# BLE.net
KiCad netlist of a schematic drawn in Altium Designer
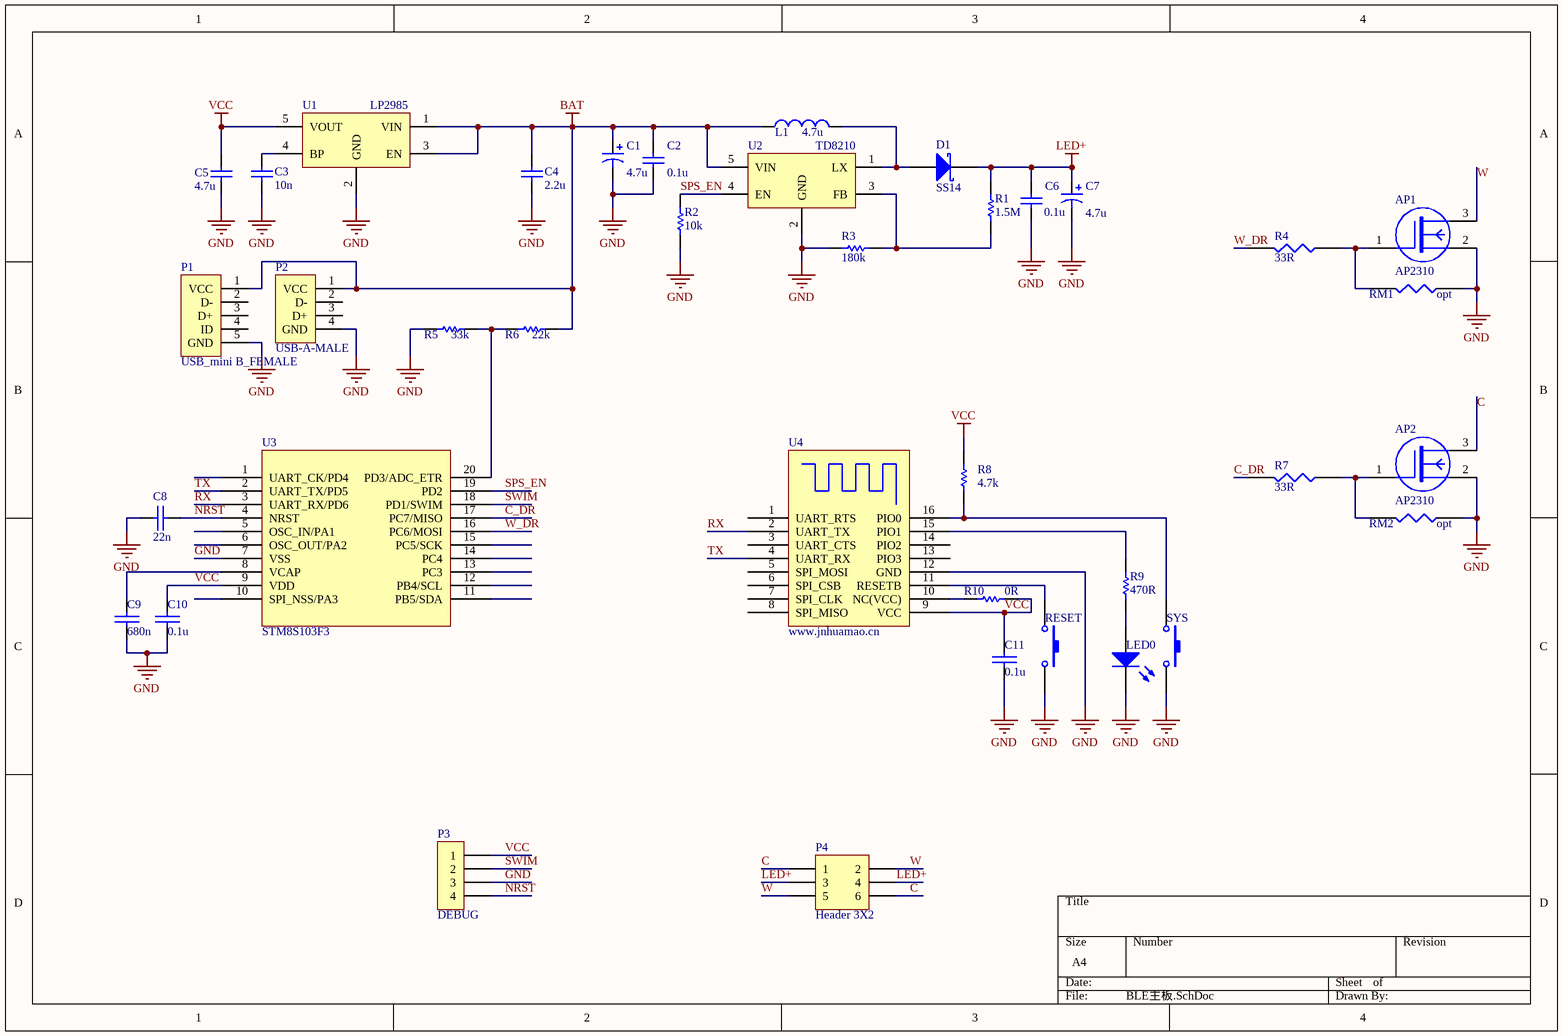
[diagram p0: BLE主板.SchDoc]

(export (version "E")
  (design (tool "Eeschema 10.0.6"))
  (components
    (comp (ref "AP1") (value "AP2310") (footprint "SOT23-3N") (libsource (lib "*") (part "MOSFET-N1")))
    (comp (ref "AP2") (value "AP2310") (footprint "SOT23-3N") (libsource (lib "*") (part "MOSFET-N1")))
    (comp (ref "C1")
      (value "4.7u")
      (footprint "2012[0805]")
      (description "Polarized Capacitor (Radial)")
      (fields (field (name "PUBLISHER") "Altium Limited"))
      (libsource (lib "Miscellaneous Devices") (part "Cap Pol1"))
    )
    (comp (ref "C2")
      (value "0.1u")
      (footprint "2012[0805]")
      (description "Capacitor")
      (fields (field (name "PUBLISHER") "Altium Limited"))
      (libsource (lib "Miscellaneous Devices") (part "Cap"))
    )
    (comp (ref "C3")
      (value "10n")
      (footprint "2012[0805]")
      (description "Capacitor")
      (fields (field (name "PUBLISHER") "Altium Limited"))
      (libsource (lib "Miscellaneous Devices") (part "Cap"))
    )
    (comp (ref "C4")
      (value "2.2u")
      (footprint "2012[0805]")
      (description "Capacitor")
      (fields (field (name "PUBLISHER") "Altium Limited"))
      (libsource (lib "Miscellaneous Devices") (part "Cap"))
    )
    (comp (ref "C5")
      (value "4.7u")
      (footprint "2012[0805]")
      (description "Capacitor")
      (fields (field (name "PUBLISHER") "Altium Limited"))
      (libsource (lib "Miscellaneous Devices") (part "Cap"))
    )
    (comp (ref "C6")
      (value "0.1u")
      (footprint "2012[0805]")
      (description "Capacitor")
      (fields (field (name "PUBLISHER") "Altium Limited"))
      (libsource (lib "Miscellaneous Devices") (part "Cap"))
    )
    (comp (ref "C7")
      (value "4.7u")
      (footprint "2012[0805]")
      (description "Polarized Capacitor (Radial)")
      (fields (field (name "PUBLISHER") "Altium Limited"))
      (libsource (lib "Miscellaneous Devices") (part "Cap Pol1"))
    )
    (comp (ref "C8")
      (value "22n")
      (footprint "2012[0805]")
      (description "Capacitor")
      (libsource (lib "*") (part "CAP"))
    )
    (comp (ref "C9")
      (value "680n")
      (footprint "2012[0805]")
      (description "Capacitor")
      (libsource (lib "*") (part "CAP"))
    )
    (comp (ref "C10")
      (value "0.1u")
      (footprint "2012[0805]")
      (description "Capacitor")
      (libsource (lib "*") (part "CAP"))
    )
    (comp (ref "C11")
      (value "0.1u")
      (footprint "2012[0805]")
      (description "Capacitor")
      (libsource (lib "*") (part "CAP"))
    )
    (comp (ref "D1")
      (value "SS14")
      (footprint "DIOM4227X23N[DO-214AC(SMA)]")
      (description "Schottky Diode")
      (fields (field (name "PUBLISHER") "Altium Limited"))
      (libsource (lib "Miscellaneous Devices") (part "D Schottky"))
    )
    (comp (ref "DS1")
      (value "LED0")
      (footprint "RESC2012N")
      (description "Typical INFRARED GaAs LED")
      (fields (field (name "PUBLISHER") "Altium Limited"))
      (libsource (lib "Miscellaneous Devices") (part "LED0"))
    )
    (comp (ref "L1")
      (value "4.7u")
      (footprint "INDP7070X40N")
      (description "Inductor")
      (fields (field (name "PUBLISHER") "Altium Limited"))
      (libsource (lib "Miscellaneous Devices") (part "Inductor"))
    )
    (comp (ref "P1")
      (value "USB_mini B_FEMALE")
      (footprint "USB/SM0.8-6H5")
      (description "Header, 5-Pin")
      (fields (field (name "PUBLISHER") "Altium Limited"))
      (libsource (lib "Miscellaneous Connectors") (part "Header 5"))
    )
    (comp (ref "P2")
      (value "USB-A-MALE")
      (footprint "USB/SM2.5-4H4")
      (description "Header, 4-Pin")
      (fields (field (name "PUBLISHER") "Altium Limited"))
      (libsource (lib "Miscellaneous Connectors") (part "Header 4"))
    )
    (comp (ref "P3")
      (value "DEBUG")
      (footprint "HDR1X4")
      (description "Connector")
      (libsource (lib "*") (part "CON4"))
    )
    (comp (ref "P4")
      (value "Header 3X2")
      (footprint "HDR2X3")
      (description "Header, 3-Pin, Dual row")
      (fields (field (name "PUBLISHER") "Altium Limited"))
      (libsource (lib "Miscellaneous Connectors") (part "Header 3X2"))
    )
    (comp (ref "R1")
      (value "1.5M")
      (footprint "2012[0805]")
      (description "Resistor")
      (fields (field (name "PUBLISHER") "Altium Limited"))
      (libsource (lib "") (part "Res1_1"))
    )
    (comp (ref "R2")
      (value "10k")
      (footprint "2012[0805]")
      (description "Resistor")
      (fields (field (name "PUBLISHER") "Altium Limited"))
      (libsource (lib "") (part "Res1_1"))
    )
    (comp (ref "R3")
      (value "180k")
      (footprint "2012[0805]")
      (description "Resistor")
      (fields (field (name "PUBLISHER") "Altium Limited"))
      (libsource (lib "") (part "Res1_1"))
    )
    (comp (ref "R4") (value "33R") (footprint "2012[0805]") (libsource (lib "*") (part "RES1")))
    (comp (ref "R5")
      (value "33k")
      (footprint "2012[0805]")
      (description "Resistor")
      (fields (field (name "PUBLISHER") "Altium Limited"))
      (libsource (lib "") (part "Res1_1"))
    )
    (comp (ref "R6")
      (value "22k")
      (footprint "2012[0805]")
      (description "Resistor")
      (fields (field (name "PUBLISHER") "Altium Limited"))
      (libsource (lib "") (part "Res1_1"))
    )
    (comp (ref "R7") (value "33R") (footprint "2012[0805]") (libsource (lib "*") (part "RES1")))
    (comp (ref "R8")
      (value "4.7k")
      (footprint "2012[0805]")
      (description "Resistor")
      (fields (field (name "PUBLISHER") "Altium Limited"))
      (libsource (lib "Miscellaneous Devices") (part "Res1"))
    )
    (comp (ref "R9")
      (value "470R")
      (footprint "2012[0805]")
      (description "Resistor")
      (fields (field (name "Comment") "Res1") (field (name "PUBLISHER") "Altium Limited"))
      (libsource (lib "Miscellaneous Devices") (part "Res1"))
    )
    (comp (ref "R10")
      (value "0R")
      (footprint "2012[0805]")
      (description "Resistor")
      (fields (field (name "PUBLISHER") "Altium Limited"))
      (libsource (lib "") (part "Res1_1"))
    )
    (comp (ref "RM1") (value "opt") (footprint "2012[0805]") (libsource (lib "*") (part "RES1")))
    (comp (ref "RM2") (value "opt") (footprint "2012[0805]") (libsource (lib "*") (part "RES1")))
    (comp (ref "S1")
      (value "RESET")
      (footprint "微动开关")
      (description "Switch")
      (fields (field (name "PUBLISHER") "Altium Limited"))
      (libsource (lib "Miscellaneous Devices") (part "SW-PB"))
    )
    (comp (ref "S2")
      (value "SYS")
      (footprint "微动开关")
      (description "Switch")
      (fields (field (name "PUBLISHER") "Altium Limited"))
      (libsource (lib "Miscellaneous Devices") (part "SW-PB"))
    )
    (comp (ref "U1") (value "LP2985") (footprint "SOT23-5AN") (libsource (lib "My Library") (part "LP2985")))
    (comp (ref "U2") (value "TD8210") (footprint "SOT23-5AN") (libsource (lib "My Library") (part "TD8210")))
    (comp (ref "U3")
      (value "STM8S103F3")
      (footprint "TSOP65P640-20BN")
      (libsource (lib "*") (part "Component_1"))
    )
    (comp (ref "U4")
      (value "www.jnhuamao.cn")
      (footprint "HM_05_06_07_11")
      (description "HM bluetooth module HM-05,HM-06,HM-07, HM-11")
      (libsource (lib "My Library") (part "HM_05_06_07_11"))
    )
  )
  (nets
    (net (code "1") (name "/C") (class "Default")
      (node (ref "AP2") (pin "3") (pinfunction "D_3") (pintype "passive"))
      (node (ref "P4") (pin "1") (pinfunction "1_1") (pintype "passive"))
      (node (ref "P4") (pin "6") (pinfunction "6_6") (pintype "passive"))
    )
    (net (code "2") (name "/C_DR") (class "Default")
      (node (ref "R7") (pin "2") (pinfunction "2_2") (pintype "passive"))
      (node (ref "U3") (pin "17") (pinfunction "PC7/MISO_17") (pintype "passive"))
    )
    (net (code "3") (name "/NRST") (class "Default")
      (node (ref "C8") (pin "2") (pinfunction "2_2") (pintype "passive"))
      (node (ref "P3") (pin "4") (pinfunction "4_4") (pintype "passive"))
      (node (ref "U3") (pin "4") (pinfunction "NRST_4") (pintype "passive"))
    )
    (net (code "4") (name "/RX") (class "Default")
      (node (ref "U3") (pin "3") (pinfunction "UART_RX/PD6_3") (pintype "passive"))
      (node (ref "U4") (pin "2") (pinfunction "UART_TX_2") (pintype "passive"))
    )
    (net (code "5") (name "/SPS_EN") (class "Default")
      (node (ref "R2") (pin "2") (pinfunction "2_2") (pintype "passive"))
      (node (ref "U2") (pin "4") (pinfunction "EN_4") (pintype "passive"))
      (node (ref "U3") (pin "19") (pinfunction "PD2_19") (pintype "passive"))
    )
    (net (code "6") (name "/SWIM") (class "Default")
      (node (ref "P3") (pin "2") (pinfunction "2_2") (pintype "passive"))
      (node (ref "U3") (pin "18") (pinfunction "PD1/SWIM_18") (pintype "passive"))
    )
    (net (code "7") (name "/TX") (class "Default")
      (node (ref "U3") (pin "2") (pinfunction "UART_TX/PD5_2") (pintype "passive"))
      (node (ref "U4") (pin "4") (pinfunction "UART_RX_4") (pintype "passive"))
    )
    (net (code "8") (name "/W") (class "Default")
      (node (ref "AP1") (pin "3") (pinfunction "D_3") (pintype "passive"))
      (node (ref "P4") (pin "2") (pinfunction "2_2") (pintype "passive"))
      (node (ref "P4") (pin "5") (pinfunction "5_5") (pintype "passive"))
    )
    (net (code "9") (name "/W_DR") (class "Default")
      (node (ref "R4") (pin "2") (pinfunction "2_2") (pintype "passive"))
      (node (ref "U3") (pin "16") (pinfunction "PC6/MOSI_16") (pintype "passive"))
    )
    (net (code "10") (name "BAT") (class "Default")
      (node (ref "C1") (pin "1") (pinfunction "1_1") (pintype "passive"))
      (node (ref "C2") (pin "1") (pinfunction "1_1") (pintype "passive"))
      (node (ref "C4") (pin "2") (pinfunction "2_2") (pintype "passive"))
      (node (ref "L1") (pin "1") (pinfunction "1_1") (pintype "passive"))
      (node (ref "P1") (pin "1") (pinfunction "VCC_1") (pintype "passive"))
      (node (ref "P2") (pin "1") (pinfunction "VCC_1") (pintype "passive"))
      (node (ref "R6") (pin "2") (pinfunction "2_2") (pintype "passive"))
      (node (ref "U1") (pin "1") (pinfunction "VIN_1") (pintype "passive"))
      (node (ref "U1") (pin "3") (pinfunction "EN_3") (pintype "passive"))
      (node (ref "U2") (pin "5") (pinfunction "VIN_5") (pintype "passive"))
    )
    (net (code "11") (name "GND") (class "Default")
      (node (ref "AP1") (pin "2") (pinfunction "S_2") (pintype "passive"))
      (node (ref "AP2") (pin "2") (pinfunction "S_2") (pintype "passive"))
      (node (ref "C1") (pin "2") (pinfunction "2_2") (pintype "passive"))
      (node (ref "C10") (pin "1") (pinfunction "1_1") (pintype "passive"))
      (node (ref "C11") (pin "1") (pinfunction "1_1") (pintype "passive"))
      (node (ref "C2") (pin "2") (pinfunction "2_2") (pintype "passive"))
      (node (ref "C3") (pin "1") (pinfunction "1_1") (pintype "passive"))
      (node (ref "C4") (pin "1") (pinfunction "1_1") (pintype "passive"))
      (node (ref "C5") (pin "1") (pinfunction "1_1") (pintype "passive"))
      (node (ref "C6") (pin "1") (pinfunction "1_1") (pintype "passive"))
      (node (ref "C7") (pin "2") (pinfunction "2_2") (pintype "passive"))
      (node (ref "C8") (pin "1") (pinfunction "1_1") (pintype "passive"))
      (node (ref "C9") (pin "1") (pinfunction "1_1") (pintype "passive"))
      (node (ref "DS1") (pin "2") (pinfunction "K_2") (pintype "passive"))
      (node (ref "P1") (pin "5") (pinfunction "GND_5") (pintype "passive"))
      (node (ref "P2") (pin "4") (pinfunction "GND_4") (pintype "passive"))
      (node (ref "P3") (pin "3") (pinfunction "3_3") (pintype "passive"))
      (node (ref "R2") (pin "1") (pinfunction "1_1") (pintype "passive"))
      (node (ref "R3") (pin "1") (pinfunction "1_1") (pintype "passive"))
      (node (ref "R5") (pin "1") (pinfunction "1_1") (pintype "passive"))
      (node (ref "RM1") (pin "1") (pinfunction "1_1") (pintype "passive"))
      (node (ref "RM2") (pin "1") (pinfunction "1_1") (pintype "passive"))
      (node (ref "S1") (pin "2") (pinfunction "2_2") (pintype "passive"))
      (node (ref "S2") (pin "2") (pinfunction "2_2") (pintype "passive"))
      (node (ref "U1") (pin "2") (pinfunction "GND_2") (pintype "passive"))
      (node (ref "U2") (pin "2") (pinfunction "GND_2") (pintype "passive"))
      (node (ref "U3") (pin "7") (pinfunction "VSS_7") (pintype "passive"))
      (node (ref "U4") (pin "12") (pinfunction "GND_12") (pintype "passive"))
    )
    (net (code "12") (name "LED+") (class "Default")
      (node (ref "C6") (pin "2") (pinfunction "2_2") (pintype "passive"))
      (node (ref "C7") (pin "1") (pinfunction "1_1") (pintype "passive"))
      (node (ref "D1") (pin "2") (pinfunction "K_2") (pintype "passive"))
      (node (ref "P4") (pin "3") (pinfunction "3_3") (pintype "passive"))
      (node (ref "P4") (pin "4") (pinfunction "4_4") (pintype "passive"))
      (node (ref "R1") (pin "2") (pinfunction "2_2") (pintype "passive"))
    )
    (net (code "13") (name "Net-(AP1-G)") (class "Default")
      (node (ref "AP1") (pin "1") (pinfunction "G_1") (pintype "passive"))
      (node (ref "R4") (pin "1") (pinfunction "1_1") (pintype "passive"))
      (node (ref "RM1") (pin "2") (pinfunction "2_2") (pintype "passive"))
    )
    (net (code "14") (name "Net-(AP2-G)") (class "Default")
      (node (ref "AP2") (pin "1") (pinfunction "G_1") (pintype "passive"))
      (node (ref "R7") (pin "1") (pinfunction "1_1") (pintype "passive"))
      (node (ref "RM2") (pin "2") (pinfunction "2_2") (pintype "passive"))
    )
    (net (code "15") (name "Net-(D1-A)") (class "Default")
      (node (ref "D1") (pin "1") (pinfunction "A_1") (pintype "passive"))
      (node (ref "L1") (pin "2") (pinfunction "2_2") (pintype "passive"))
      (node (ref "U2") (pin "1") (pinfunction "LX_1") (pintype "passive"))
    )
    (net (code "16") (name "Net-(DS1-A)") (class "Default")
      (node (ref "DS1") (pin "1") (pinfunction "A_1") (pintype "passive"))
      (node (ref "R9") (pin "2") (pinfunction "2_2") (pintype "passive"))
    )
    (net (code "17") (name "Net-(U1-BP)") (class "Default")
      (node (ref "C3") (pin "2") (pinfunction "2_2") (pintype "passive"))
      (node (ref "U1") (pin "4") (pinfunction "BP_4") (pintype "passive"))
    )
    (net (code "18") (name "Net-(U2-FB)") (class "Default")
      (node (ref "R1") (pin "1") (pinfunction "1_1") (pintype "passive"))
      (node (ref "R3") (pin "2") (pinfunction "2_2") (pintype "passive"))
      (node (ref "U2") (pin "3") (pinfunction "FB_3") (pintype "passive"))
    )
    (net (code "19") (name "Net-(U3-PD3{slash}ADC_ETR)") (class "Default")
      (node (ref "R5") (pin "2") (pinfunction "2_2") (pintype "passive"))
      (node (ref "R6") (pin "1") (pinfunction "1_1") (pintype "passive"))
      (node (ref "U3") (pin "20") (pinfunction "PD3/ADC_ETR_20") (pintype "passive"))
    )
    (net (code "20") (name "Net-(U3-VCAP)") (class "Default")
      (node (ref "C9") (pin "2") (pinfunction "2_2") (pintype "passive"))
      (node (ref "U3") (pin "8") (pinfunction "VCAP_8") (pintype "passive"))
    )
    (net (code "21") (name "Net-(U4-NC(VCC))") (class "Default")
      (node (ref "R10") (pin "1") (pinfunction "1_1") (pintype "passive"))
      (node (ref "U4") (pin "10") (pinfunction "NC(VCC)_10") (pintype "passive"))
    )
    (net (code "22") (name "Net-(U4-PIO0)") (class "Default")
      (node (ref "R8") (pin "2") (pinfunction "2_2") (pintype "passive"))
      (node (ref "S2") (pin "1") (pinfunction "1_1") (pintype "passive"))
      (node (ref "U4") (pin "16") (pinfunction "PIO0_16") (pintype "passive"))
    )
    (net (code "23") (name "Net-(U4-PIO1)") (class "Default")
      (node (ref "R9") (pin "1") (pinfunction "1_1") (pintype "passive"))
      (node (ref "U4") (pin "15") (pinfunction "PIO1_15") (pintype "passive"))
    )
    (net (code "24") (name "Net-(U4-RESETB)") (class "Default")
      (node (ref "S1") (pin "1") (pinfunction "1_1") (pintype "passive"))
      (node (ref "U4") (pin "11") (pinfunction "RESETB_11") (pintype "passive"))
    )
    (net (code "25") (name "VCC") (class "Default")
      (node (ref "C10") (pin "2") (pinfunction "2_2") (pintype "passive"))
      (node (ref "C11") (pin "2") (pinfunction "2_2") (pintype "passive"))
      (node (ref "C5") (pin "2") (pinfunction "2_2") (pintype "passive"))
      (node (ref "P3") (pin "1") (pinfunction "1_1") (pintype "passive"))
      (node (ref "R10") (pin "2") (pinfunction "2_2") (pintype "passive"))
      (node (ref "R8") (pin "1") (pinfunction "1_1") (pintype "passive"))
      (node (ref "U1") (pin "5") (pinfunction "VOUT_5") (pintype "passive"))
      (node (ref "U3") (pin "9") (pinfunction "VDD_9") (pintype "passive"))
      (node (ref "U4") (pin "9") (pinfunction "VCC_9") (pintype "passive"))
    )
    (net (code "26") (name "unconnected-(P1-D+-Pad3)") (class "Default")
      (node (ref "P1") (pin "3") (pinfunction "D+_3") (pintype "passive"))
    )
    (net (code "27") (name "unconnected-(P1-D--Pad2)") (class "Default")
      (node (ref "P1") (pin "2") (pinfunction "D-_2") (pintype "passive"))
    )
    (net (code "28") (name "unconnected-(P1-ID-Pad4)") (class "Default")
      (node (ref "P1") (pin "4") (pinfunction "ID_4") (pintype "passive"))
    )
    (net (code "29") (name "unconnected-(P2-D+-Pad3)") (class "Default")
      (node (ref "P2") (pin "3") (pinfunction "D+_3") (pintype "passive"))
    )
    (net (code "30") (name "unconnected-(P2-D--Pad2)") (class "Default")
      (node (ref "P2") (pin "2") (pinfunction "D-_2") (pintype "passive"))
    )
    (net (code "31") (name "unconnected-(U3-OSC_IN{slash}PA1-Pad5)") (class "Default")
      (node (ref "U3") (pin "5") (pinfunction "OSC_IN/PA1_5") (pintype "passive"))
    )
    (net (code "32") (name "unconnected-(U3-OSC_OUT{slash}PA2-Pad6)") (class "Default")
      (node (ref "U3") (pin "6") (pinfunction "OSC_OUT/PA2_6") (pintype "passive"))
    )
    (net (code "33") (name "unconnected-(U3-PB4{slash}SCL-Pad12)") (class "Default")
      (node (ref "U3") (pin "12") (pinfunction "PB4/SCL_12") (pintype "passive"))
    )
    (net (code "34") (name "unconnected-(U3-PB5{slash}SDA-Pad11)") (class "Default")
      (node (ref "U3") (pin "11") (pinfunction "PB5/SDA_11") (pintype "passive"))
    )
    (net (code "35") (name "unconnected-(U3-PC3-Pad13)") (class "Default")
      (node (ref "U3") (pin "13") (pinfunction "PC3_13") (pintype "passive"))
    )
    (net (code "36") (name "unconnected-(U3-PC4-Pad14)") (class "Default")
      (node (ref "U3") (pin "14") (pinfunction "PC4_14") (pintype "passive"))
    )
    (net (code "37") (name "unconnected-(U3-PC5{slash}SCK-Pad15)") (class "Default")
      (node (ref "U3") (pin "15") (pinfunction "PC5/SCK_15") (pintype "passive"))
    )
    (net (code "38") (name "unconnected-(U3-SPI_NSS{slash}PA3-Pad10)") (class "Default")
      (node (ref "U3") (pin "10") (pinfunction "SPI_NSS/PA3_10") (pintype "passive"))
    )
    (net (code "39") (name "unconnected-(U3-UART_CK{slash}PD4-Pad1)") (class "Default")
      (node (ref "U3") (pin "1") (pinfunction "UART_CK/PD4_1") (pintype "passive"))
    )
    (net (code "40") (name "unconnected-(U4-PIO2-Pad14)") (class "Default")
      (node (ref "U4") (pin "14") (pinfunction "PIO2_14") (pintype "passive"))
    )
    (net (code "41") (name "unconnected-(U4-PIO3-Pad13)") (class "Default")
      (node (ref "U4") (pin "13") (pinfunction "PIO3_13") (pintype "passive"))
    )
    (net (code "42") (name "unconnected-(U4-SPI_CLK-Pad7)") (class "Default")
      (node (ref "U4") (pin "7") (pinfunction "SPI_CLK_7") (pintype "passive"))
    )
    (net (code "43") (name "unconnected-(U4-SPI_CSB-Pad6)") (class "Default")
      (node (ref "U4") (pin "6") (pinfunction "SPI_CSB_6") (pintype "passive"))
    )
    (net (code "44") (name "unconnected-(U4-SPI_MISO-Pad8)") (class "Default")
      (node (ref "U4") (pin "8") (pinfunction "SPI_MISO_8") (pintype "passive"))
    )
    (net (code "45") (name "unconnected-(U4-SPI_MOSI-Pad5)") (class "Default")
      (node (ref "U4") (pin "5") (pinfunction "SPI_MOSI_5") (pintype "passive"))
    )
    (net (code "46") (name "unconnected-(U4-UART_CTS-Pad3)") (class "Default")
      (node (ref "U4") (pin "3") (pinfunction "UART_CTS_3") (pintype "passive"))
    )
    (net (code "47") (name "unconnected-(U4-UART_RTS-Pad1)") (class "Default")
      (node (ref "U4") (pin "1") (pinfunction "UART_RTS_1") (pintype "passive"))
    )
  )
)
